# 2-FrontEnd.net
KiCad netlist of a schematic drawn in Altium Designer
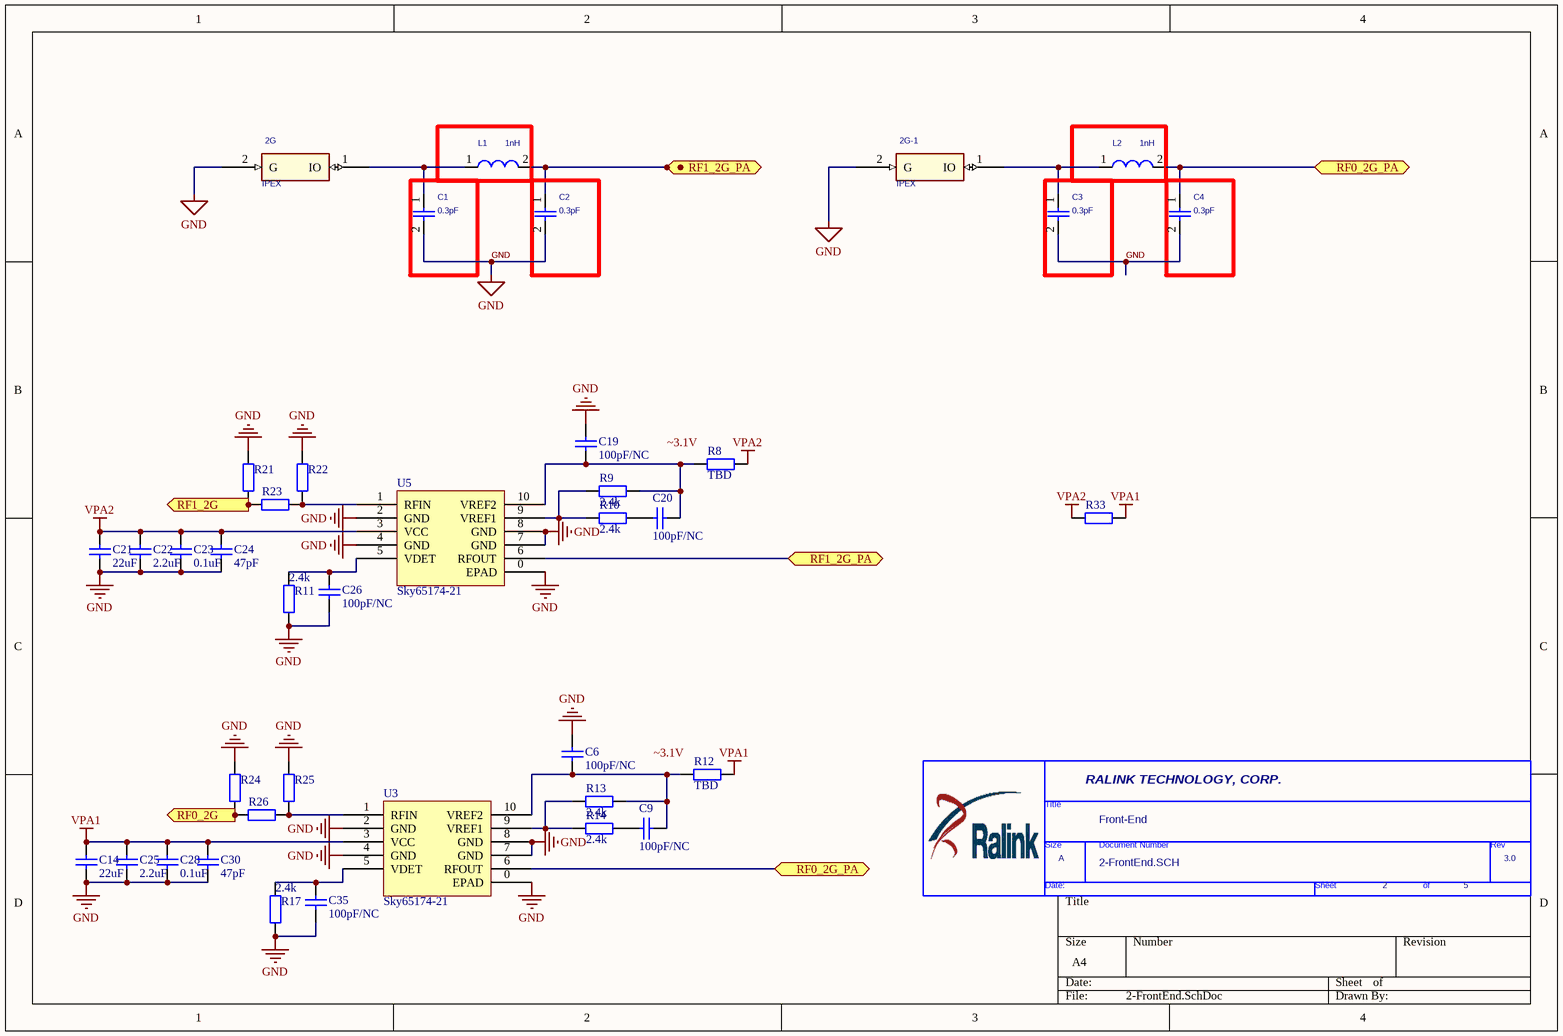
[diagram p0: 2-FrontEnd.SchDoc]

(export (version "E")
  (design (tool "Eeschema 10.0.6"))
  (components
    (comp (ref "2G") (value "IPEX") (footprint "IPEX") (libsource (lib "*") (part "ANT-RA-USB-1")))
    (comp (ref "2G-1") (value "IPEX") (footprint "IPEX") (libsource (lib "*") (part "ANT-RA-USB-1")))
    (comp (ref "C1") (value "0.3pF") (footprint "0402") (libsource (lib "*") (part "CAP/0402")))
    (comp (ref "C2") (value "0.3pF") (footprint "0402") (libsource (lib "*") (part "CAP/0402")))
    (comp (ref "C3") (value "0.3pF") (footprint "0402") (libsource (lib "*") (part "CAP/0402")))
    (comp (ref "C4") (value "0.3pF") (footprint "0402") (libsource (lib "*") (part "CAP/0402")))
    (comp (ref "C6")
      (value "100pF/NC")
      (footprint "0402")
      (description "Capacitor")
      (fields (field (name "Comment") "Cap") (field (name "PUBLISHER") "Altium Limited"))
      (libsource (lib "RTC6705") (part "Cap"))
    )
    (comp (ref "C9")
      (value "100pF/NC")
      (footprint "0402")
      (description "Capacitor")
      (fields (field (name "Comment") "Cap") (field (name "PUBLISHER") "Altium Limited"))
      (libsource (lib "RTC6705") (part "Cap"))
    )
    (comp (ref "C14")
      (value "22uF")
      (footprint "0805")
      (description "Capacitor")
      (fields (field (name "Comment") "Cap") (field (name "PUBLISHER") "Altium Limited"))
      (libsource (lib "RTC6705") (part "Cap"))
    )
    (comp (ref "C19")
      (value "100pF/NC")
      (footprint "0402")
      (description "Capacitor")
      (fields (field (name "Comment") "Cap") (field (name "PUBLISHER") "Altium Limited"))
      (libsource (lib "RTC6705") (part "Cap"))
    )
    (comp (ref "C20")
      (value "100pF/NC")
      (footprint "0402")
      (description "Capacitor")
      (fields (field (name "Comment") "Cap") (field (name "PUBLISHER") "Altium Limited"))
      (libsource (lib "RTC6705") (part "Cap"))
    )
    (comp (ref "C21")
      (value "22uF")
      (footprint "0805")
      (description "Capacitor")
      (fields (field (name "Comment") "Cap") (field (name "PUBLISHER") "Altium Limited"))
      (libsource (lib "RTC6705") (part "Cap"))
    )
    (comp (ref "C22")
      (value "2.2uF")
      (footprint "0603")
      (description "Capacitor")
      (fields (field (name "Comment") "Cap") (field (name "PUBLISHER") "Altium Limited"))
      (libsource (lib "RTC6705") (part "Cap"))
    )
    (comp (ref "C23")
      (value "0.1uF")
      (footprint "0402")
      (description "Capacitor")
      (fields (field (name "Comment") "Cap") (field (name "PUBLISHER") "Altium Limited"))
      (libsource (lib "RTC6705") (part "Cap"))
    )
    (comp (ref "C24")
      (value "47pF")
      (footprint "0402")
      (description "Capacitor")
      (fields (field (name "Comment") "Cap") (field (name "PUBLISHER") "Altium Limited"))
      (libsource (lib "RTC6705") (part "Cap"))
    )
    (comp (ref "C25")
      (value "2.2uF")
      (footprint "0603")
      (description "Capacitor")
      (fields (field (name "Comment") "Cap") (field (name "PUBLISHER") "Altium Limited"))
      (libsource (lib "RTC6705") (part "Cap"))
    )
    (comp (ref "C26")
      (value "100pF/NC")
      (footprint "0402")
      (description "Capacitor")
      (fields (field (name "Comment") "Cap") (field (name "PUBLISHER") "Altium Limited"))
      (libsource (lib "RTC6705") (part "Cap"))
    )
    (comp (ref "C28")
      (value "0.1uF")
      (footprint "0402")
      (description "Capacitor")
      (fields (field (name "Comment") "Cap") (field (name "PUBLISHER") "Altium Limited"))
      (libsource (lib "RTC6705") (part "Cap"))
    )
    (comp (ref "C30")
      (value "47pF")
      (footprint "0402")
      (description "Capacitor")
      (fields (field (name "Comment") "Cap") (field (name "PUBLISHER") "Altium Limited"))
      (libsource (lib "RTC6705") (part "Cap"))
    )
    (comp (ref "C35")
      (value "100pF/NC")
      (footprint "0402")
      (description "Capacitor")
      (fields (field (name "Comment") "Cap") (field (name "PUBLISHER") "Altium Limited"))
      (libsource (lib "RTC6705") (part "Cap"))
    )
    (comp (ref "L1") (value "1nH") (footprint "0402") (libsource (lib "*") (part "L/0402")))
    (comp (ref "L2") (value "1nH") (footprint "0402") (libsource (lib "*") (part "L/0402")))
    (comp (ref "R8")
      (value "TBD")
      (footprint "0402")
      (description "Resistor")
      (fields (field (name "Comment") "Res2") (field (name "PUBLISHER") "Altium Limited"))
      (libsource (lib "RTC6705") (part "Res2"))
    )
    (comp (ref "R9")
      (value "2.4k")
      (footprint "0402")
      (description "Resistor")
      (fields (field (name "Comment") "Res2") (field (name "PUBLISHER") "Altium Limited"))
      (libsource (lib "RTC6705") (part "Res2"))
    )
    (comp (ref "R10")
      (value "2.4k")
      (footprint "0402")
      (description "Resistor")
      (fields (field (name "Comment") "Res2") (field (name "PUBLISHER") "Altium Limited"))
      (libsource (lib "RTC6705") (part "Res2"))
    )
    (comp (ref "R11")
      (value "2.4k")
      (footprint "0402")
      (description "Resistor")
      (fields (field (name "Comment") "Res2") (field (name "PUBLISHER") "Altium Limited"))
      (libsource (lib "") (part "Res2_1"))
    )
    (comp (ref "R12")
      (value "TBD")
      (footprint "0402")
      (description "Resistor")
      (fields (field (name "Comment") "Res2") (field (name "PUBLISHER") "Altium Limited"))
      (libsource (lib "RTC6705") (part "Res2"))
    )
    (comp (ref "R13")
      (value "2.4k")
      (footprint "0402")
      (description "Resistor")
      (fields (field (name "Comment") "Res2") (field (name "PUBLISHER") "Altium Limited"))
      (libsource (lib "RTC6705") (part "Res2"))
    )
    (comp (ref "R14")
      (value "2.4k")
      (footprint "0402")
      (description "Resistor")
      (fields (field (name "Comment") "Res2") (field (name "PUBLISHER") "Altium Limited"))
      (libsource (lib "RTC6705") (part "Res2"))
    )
    (comp (ref "R17")
      (value "2.4k")
      (footprint "0402")
      (description "Resistor")
      (fields (field (name "Comment") "Res2") (field (name "PUBLISHER") "Altium Limited"))
      (libsource (lib "") (part "Res2_1"))
    )
    (comp (ref "R21")
      (value "TBD")
      (footprint "0402")
      (description "Resistor")
      (fields (field (name "PUBLISHER") "Altium Limited"))
      (libsource (lib "") (part "Res2_1"))
    )
    (comp (ref "R22")
      (value "TBD")
      (footprint "0402")
      (description "Resistor")
      (fields (field (name "PUBLISHER") "Altium Limited"))
      (libsource (lib "") (part "Res2_2"))
    )
    (comp (ref "R23")
      (value "TBD")
      (footprint "0402")
      (description "Resistor")
      (fields (field (name "PUBLISHER") "Altium Limited"))
      (libsource (lib "") (part "Res2_3"))
    )
    (comp (ref "R24")
      (value "TBD")
      (footprint "0402")
      (description "Resistor")
      (fields (field (name "PUBLISHER") "Altium Limited"))
      (libsource (lib "") (part "Res2_2"))
    )
    (comp (ref "R25")
      (value "TBD")
      (footprint "0402")
      (description "Resistor")
      (fields (field (name "PUBLISHER") "Altium Limited"))
      (libsource (lib "") (part "Res2_2"))
    )
    (comp (ref "R26")
      (value "TBD")
      (footprint "0402")
      (description "Resistor")
      (fields (field (name "PUBLISHER") "Altium Limited"))
      (libsource (lib "") (part "Res2_3"))
    )
    (comp (ref "R33")
      (value "NC/0R")
      (footprint "0402")
      (description "Resistor")
      (fields (field (name "PUBLISHER") "Altium Limited"))
      (libsource (lib "") (part "Res2_3"))
    )
    (comp (ref "U3")
      (value "Sky65174-21")
      (footprint "SKY65174-21")
      (libsource (lib "WifiGain") (part "Sky65174-21"))
    )
    (comp (ref "U5")
      (value "Sky65174-21")
      (footprint "SKY65174-21")
      (libsource (lib "WifiGain") (part "Sky65174-21"))
    )
  )
  (nets
    (net (code "1") (name "/RF0_2G") (class "Default")
      (node (ref "R24") (pin "2") (pinfunction "2_2") (pintype "passive"))
      (node (ref "R26") (pin "1") (pinfunction "1_1") (pintype "passive"))
    )
    (net (code "2") (name "/RF0_2G_PA") (class "Default")
      (node (ref "C4") (pin "1") (pinfunction "1_1") (pintype "passive"))
      (node (ref "L2") (pin "2") (pinfunction "2_2") (pintype "passive"))
      (node (ref "U3") (pin "6") (pinfunction "RFOUT_6") (pintype "passive"))
    )
    (net (code "3") (name "/RF1_2G") (class "Default")
      (node (ref "R21") (pin "1") (pinfunction "1_1") (pintype "passive"))
      (node (ref "R23") (pin "1") (pinfunction "1_1") (pintype "passive"))
    )
    (net (code "4") (name "/RF1_2G_PA") (class "Default")
      (node (ref "C2") (pin "1") (pinfunction "1_1") (pintype "passive"))
      (node (ref "L1") (pin "2") (pinfunction "2_2") (pintype "passive"))
      (node (ref "U5") (pin "6") (pinfunction "RFOUT_6") (pintype "passive"))
    )
    (net (code "6") (name "GND") (class "Default")
      (node (ref "2G") (pin "2") (pinfunction "G_2") (pintype "input"))
      (node (ref "2G-1") (pin "2") (pinfunction "G_2") (pintype "input"))
      (node (ref "C1") (pin "2") (pinfunction "2_2") (pintype "passive"))
      (node (ref "C14") (pin "2") (pinfunction "2_2") (pintype "passive"))
      (node (ref "C19") (pin "1") (pinfunction "1_1") (pintype "passive"))
      (node (ref "C2") (pin "2") (pinfunction "2_2") (pintype "passive"))
      (node (ref "C21") (pin "2") (pinfunction "2_2") (pintype "passive"))
      (node (ref "C22") (pin "2") (pinfunction "2_2") (pintype "passive"))
      (node (ref "C23") (pin "2") (pinfunction "2_2") (pintype "passive"))
      (node (ref "C24") (pin "2") (pinfunction "2_2") (pintype "passive"))
      (node (ref "C25") (pin "2") (pinfunction "2_2") (pintype "passive"))
      (node (ref "C26") (pin "2") (pinfunction "2_2") (pintype "passive"))
      (node (ref "C28") (pin "2") (pinfunction "2_2") (pintype "passive"))
      (node (ref "C3") (pin "2") (pinfunction "2_2") (pintype "passive"))
      (node (ref "C30") (pin "2") (pinfunction "2_2") (pintype "passive"))
      (node (ref "C35") (pin "2") (pinfunction "2_2") (pintype "passive"))
      (node (ref "C4") (pin "2") (pinfunction "2_2") (pintype "passive"))
      (node (ref "C6") (pin "1") (pinfunction "1_1") (pintype "passive"))
      (node (ref "R11") (pin "1") (pinfunction "1_1") (pintype "passive"))
      (node (ref "R17") (pin "1") (pinfunction "1_1") (pintype "passive"))
      (node (ref "R21") (pin "2") (pinfunction "2_2") (pintype "passive"))
      (node (ref "R22") (pin "1") (pinfunction "1_1") (pintype "passive"))
      (node (ref "R24") (pin "1") (pinfunction "1_1") (pintype "passive"))
      (node (ref "R25") (pin "1") (pinfunction "1_1") (pintype "passive"))
      (node (ref "U3") (pin "0") (pinfunction "EPAD_0") (pintype "passive"))
      (node (ref "U3") (pin "2") (pinfunction "GND_2") (pintype "passive"))
      (node (ref "U3") (pin "4") (pinfunction "GND_4") (pintype "passive"))
      (node (ref "U3") (pin "7") (pinfunction "GND_7") (pintype "passive"))
      (node (ref "U3") (pin "8") (pinfunction "GND_8") (pintype "passive"))
      (node (ref "U5") (pin "0") (pinfunction "EPAD_0") (pintype "passive"))
      (node (ref "U5") (pin "2") (pinfunction "GND_2") (pintype "passive"))
      (node (ref "U5") (pin "4") (pinfunction "GND_4") (pintype "passive"))
      (node (ref "U5") (pin "7") (pinfunction "GND_7") (pintype "passive"))
      (node (ref "U5") (pin "8") (pinfunction "GND_8") (pintype "passive"))
    )
    (net (code "7") (name "Net-(2G-1-IO)") (class "Default")
      (node (ref "2G-1") (pin "1") (pinfunction "IO_1") (pintype "bidirectional"))
      (node (ref "C3") (pin "1") (pinfunction "1_1") (pintype "passive"))
      (node (ref "L2") (pin "1") (pinfunction "1_1") (pintype "passive"))
    )
    (net (code "8") (name "Net-(2G-IO)") (class "Default")
      (node (ref "2G") (pin "1") (pinfunction "IO_1") (pintype "bidirectional"))
      (node (ref "C1") (pin "1") (pinfunction "1_1") (pintype "passive"))
      (node (ref "L1") (pin "1") (pinfunction "1_1") (pintype "passive"))
    )
    (net (code "9") (name "Net-(C9-Pad1)") (class "Default")
      (node (ref "C9") (pin "1") (pinfunction "1_1") (pintype "passive"))
      (node (ref "R14") (pin "1") (pinfunction "1_1") (pintype "passive"))
    )
    (net (code "10") (name "Net-(C20-Pad1)") (class "Default")
      (node (ref "C20") (pin "1") (pinfunction "1_1") (pintype "passive"))
      (node (ref "R10") (pin "1") (pinfunction "1_1") (pintype "passive"))
    )
    (net (code "11") (name "Net-(U3-RFIN)") (class "Default")
      (node (ref "R25") (pin "2") (pinfunction "2_2") (pintype "passive"))
      (node (ref "R26") (pin "2") (pinfunction "2_2") (pintype "passive"))
      (node (ref "U3") (pin "1") (pinfunction "RFIN_1") (pintype "passive"))
    )
    (net (code "12") (name "Net-(U3-VDET)") (class "Default")
      (node (ref "C35") (pin "1") (pinfunction "1_1") (pintype "passive"))
      (node (ref "R17") (pin "2") (pinfunction "2_2") (pintype "passive"))
      (node (ref "U3") (pin "5") (pinfunction "VDET_5") (pintype "passive"))
    )
    (net (code "13") (name "Net-(U3-VREF1)") (class "Default")
      (node (ref "R13") (pin "2") (pinfunction "2_2") (pintype "passive"))
      (node (ref "R14") (pin "2") (pinfunction "2_2") (pintype "passive"))
      (node (ref "U3") (pin "9") (pinfunction "VREF1_9") (pintype "passive"))
    )
    (net (code "14") (name "Net-(U3-VREF2)") (class "Default")
      (node (ref "C6") (pin "2") (pinfunction "2_2") (pintype "passive"))
      (node (ref "C9") (pin "2") (pinfunction "2_2") (pintype "passive"))
      (node (ref "R12") (pin "2") (pinfunction "2_2") (pintype "passive"))
      (node (ref "R13") (pin "1") (pinfunction "1_1") (pintype "passive"))
      (node (ref "U3") (pin "10") (pinfunction "VREF2_10") (pintype "passive"))
    )
    (net (code "15") (name "Net-(U5-RFIN)") (class "Default")
      (node (ref "R22") (pin "2") (pinfunction "2_2") (pintype "passive"))
      (node (ref "R23") (pin "2") (pinfunction "2_2") (pintype "passive"))
      (node (ref "U5") (pin "1") (pinfunction "RFIN_1") (pintype "passive"))
    )
    (net (code "16") (name "Net-(U5-VDET)") (class "Default")
      (node (ref "C26") (pin "1") (pinfunction "1_1") (pintype "passive"))
      (node (ref "R11") (pin "2") (pinfunction "2_2") (pintype "passive"))
      (node (ref "U5") (pin "5") (pinfunction "VDET_5") (pintype "passive"))
    )
    (net (code "17") (name "Net-(U5-VREF1)") (class "Default")
      (node (ref "R10") (pin "2") (pinfunction "2_2") (pintype "passive"))
      (node (ref "R9") (pin "2") (pinfunction "2_2") (pintype "passive"))
      (node (ref "U5") (pin "9") (pinfunction "VREF1_9") (pintype "passive"))
    )
    (net (code "18") (name "Net-(U5-VREF2)") (class "Default")
      (node (ref "C19") (pin "2") (pinfunction "2_2") (pintype "passive"))
      (node (ref "C20") (pin "2") (pinfunction "2_2") (pintype "passive"))
      (node (ref "R8") (pin "2") (pinfunction "2_2") (pintype "passive"))
      (node (ref "R9") (pin "1") (pinfunction "1_1") (pintype "passive"))
      (node (ref "U5") (pin "10") (pinfunction "VREF2_10") (pintype "passive"))
    )
    (net (code "19") (name "VPA1") (class "Default")
      (node (ref "C14") (pin "1") (pinfunction "1_1") (pintype "passive"))
      (node (ref "C25") (pin "1") (pinfunction "1_1") (pintype "passive"))
      (node (ref "C28") (pin "1") (pinfunction "1_1") (pintype "passive"))
      (node (ref "C30") (pin "1") (pinfunction "1_1") (pintype "passive"))
      (node (ref "R12") (pin "1") (pinfunction "1_1") (pintype "passive"))
      (node (ref "R33") (pin "2") (pinfunction "2_2") (pintype "passive"))
      (node (ref "U3") (pin "3") (pinfunction "VCC_3") (pintype "passive"))
    )
    (net (code "20") (name "VPA2") (class "Default")
      (node (ref "C21") (pin "1") (pinfunction "1_1") (pintype "passive"))
      (node (ref "C22") (pin "1") (pinfunction "1_1") (pintype "passive"))
      (node (ref "C23") (pin "1") (pinfunction "1_1") (pintype "passive"))
      (node (ref "C24") (pin "1") (pinfunction "1_1") (pintype "passive"))
      (node (ref "R33") (pin "1") (pinfunction "1_1") (pintype "passive"))
      (node (ref "R8") (pin "1") (pinfunction "1_1") (pintype "passive"))
      (node (ref "U5") (pin "3") (pinfunction "VCC_3") (pintype "passive"))
    )
  )
)
